# 2278657L.net
KiCad netlist of a schematic drawn in EAGLE
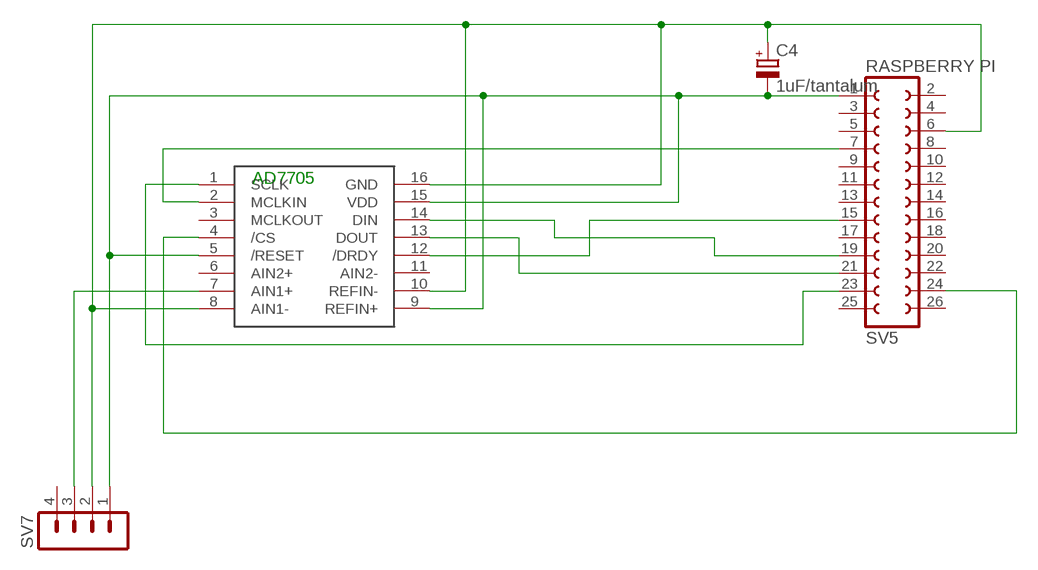
[diagram p0: schematic, sheet 1]

(export (version "E")
  (design (tool "Eeschema 10.0.6"))
  (components
    (comp (ref "C4")
      (value "1uF/tantalum")
      (footprint "eagle-import:TT2D7")
      (libsource (lib "eagle-import") (part "CPOL-EUTT2D7"))
    )
    (comp (ref "SV5")
      (value "RASPBERRY PI")
      (footprint "eagle-import:FE13-2")
      (libsource (lib "eagle-import") (part "FE13-2"))
    )
    (comp (ref "SV7")
      (value "MA04-1")
      (footprint "eagle-import:MA04-1")
      (libsource (lib "eagle-import") (part "MA04-1"))
    )
    (comp (ref "U$3")
      (value "AD7705")
      (footprint "eagle-import:DIP16")
      (libsource (lib "eagle-import") (part "AD7705"))
    )
  )
  (nets
    (net (code "1") (name "Net-(U$3-AIN1+)") (class "Default")
      (node (ref "SV7") (pin "3") (pinfunction "3_3") (pintype "passive"))
      (node (ref "U$3") (pin "7") (pinfunction "AIN1+_7") (pintype "bidirectional"))
    )
    (net (code "2") (name "Net-(U$3-AIN1-)") (class "Default")
      (node (ref "C4") (pin "+") (pinfunction "+_+") (pintype "passive"))
      (node (ref "SV5") (pin "6") (pinfunction "6_6") (pintype "passive"))
      (node (ref "SV7") (pin "2") (pinfunction "2_2") (pintype "passive"))
      (node (ref "U$3") (pin "10") (pinfunction "REFIN-_10") (pintype "bidirectional"))
      (node (ref "U$3") (pin "16") (pinfunction "GND_16") (pintype "power_in"))
      (node (ref "U$3") (pin "8") (pinfunction "AIN1-_8") (pintype "bidirectional"))
    )
    (net (code "3") (name "Net-(U$3-DIN)") (class "Default")
      (node (ref "SV5") (pin "19") (pinfunction "19_19") (pintype "passive"))
      (node (ref "U$3") (pin "14") (pinfunction "DIN_14") (pintype "bidirectional"))
    )
    (net (code "4") (name "Net-(U$3-DOUT)") (class "Default")
      (node (ref "SV5") (pin "21") (pinfunction "21_21") (pintype "passive"))
      (node (ref "U$3") (pin "13") (pinfunction "DOUT_13") (pintype "bidirectional"))
    )
    (net (code "5") (name "Net-(U$3-MCLKIN)") (class "Default")
      (node (ref "SV5") (pin "7") (pinfunction "7_7") (pintype "passive"))
      (node (ref "U$3") (pin "2") (pinfunction "MCLKIN_2") (pintype "bidirectional"))
    )
    (net (code "6") (name "Net-(U$3-REFIN+)") (class "Default")
      (node (ref "C4") (pin "-") (pinfunction "-_-") (pintype "passive"))
      (node (ref "SV5") (pin "1") (pinfunction "1_1") (pintype "passive"))
      (node (ref "SV7") (pin "1") (pinfunction "1_1") (pintype "passive"))
      (node (ref "U$3") (pin "15") (pinfunction "VDD_15") (pintype "power_in"))
      (node (ref "U$3") (pin "5") (pinfunction "/RESET_5") (pintype "bidirectional"))
      (node (ref "U$3") (pin "9") (pinfunction "REFIN+_9") (pintype "bidirectional"))
    )
    (net (code "7") (name "Net-(U$3-SCLK)") (class "Default")
      (node (ref "SV5") (pin "23") (pinfunction "23_23") (pintype "passive"))
      (node (ref "U$3") (pin "1") (pinfunction "SCLK_1") (pintype "bidirectional"))
    )
    (net (code "8") (name "Net-(U$3-{slash}CS)") (class "Default")
      (node (ref "SV5") (pin "24") (pinfunction "24_24") (pintype "passive"))
      (node (ref "U$3") (pin "4") (pinfunction "/CS_4") (pintype "bidirectional"))
    )
    (net (code "9") (name "Net-(U$3-{slash}DRDY)") (class "Default")
      (node (ref "SV5") (pin "15") (pinfunction "15_15") (pintype "passive"))
      (node (ref "U$3") (pin "12") (pinfunction "/DRDY_12") (pintype "bidirectional"))
    )
    (net (code "10") (name "unconnected-(SV5-Pad2)") (class "Default")
      (node (ref "SV5") (pin "2") (pinfunction "2_2") (pintype "passive"))
    )
    (net (code "11") (name "unconnected-(SV5-Pad3)") (class "Default")
      (node (ref "SV5") (pin "3") (pinfunction "3_3") (pintype "passive"))
    )
    (net (code "12") (name "unconnected-(SV5-Pad4)") (class "Default")
      (node (ref "SV5") (pin "4") (pinfunction "4_4") (pintype "passive"))
    )
    (net (code "13") (name "unconnected-(SV5-Pad5)") (class "Default")
      (node (ref "SV5") (pin "5") (pinfunction "5_5") (pintype "passive"))
    )
    (net (code "14") (name "unconnected-(SV5-Pad8)") (class "Default")
      (node (ref "SV5") (pin "8") (pinfunction "8_8") (pintype "passive"))
    )
    (net (code "15") (name "unconnected-(SV5-Pad9)") (class "Default")
      (node (ref "SV5") (pin "9") (pinfunction "9_9") (pintype "passive"))
    )
    (net (code "16") (name "unconnected-(SV5-Pad10)") (class "Default")
      (node (ref "SV5") (pin "10") (pinfunction "10_10") (pintype "passive"))
    )
    (net (code "17") (name "unconnected-(SV5-Pad11)") (class "Default")
      (node (ref "SV5") (pin "11") (pinfunction "11_11") (pintype "passive"))
    )
    (net (code "18") (name "unconnected-(SV5-Pad12)") (class "Default")
      (node (ref "SV5") (pin "12") (pinfunction "12_12") (pintype "passive"))
    )
    (net (code "19") (name "unconnected-(SV5-Pad13)") (class "Default")
      (node (ref "SV5") (pin "13") (pinfunction "13_13") (pintype "passive"))
    )
    (net (code "20") (name "unconnected-(SV5-Pad14)") (class "Default")
      (node (ref "SV5") (pin "14") (pinfunction "14_14") (pintype "passive"))
    )
    (net (code "21") (name "unconnected-(SV5-Pad16)") (class "Default")
      (node (ref "SV5") (pin "16") (pinfunction "16_16") (pintype "passive"))
    )
    (net (code "22") (name "unconnected-(SV5-Pad17)") (class "Default")
      (node (ref "SV5") (pin "17") (pinfunction "17_17") (pintype "passive"))
    )
    (net (code "23") (name "unconnected-(SV5-Pad18)") (class "Default")
      (node (ref "SV5") (pin "18") (pinfunction "18_18") (pintype "passive"))
    )
    (net (code "24") (name "unconnected-(SV5-Pad20)") (class "Default")
      (node (ref "SV5") (pin "20") (pinfunction "20_20") (pintype "passive"))
    )
    (net (code "25") (name "unconnected-(SV5-Pad22)") (class "Default")
      (node (ref "SV5") (pin "22") (pinfunction "22_22") (pintype "passive"))
    )
    (net (code "26") (name "unconnected-(SV5-Pad25)") (class "Default")
      (node (ref "SV5") (pin "25") (pinfunction "25_25") (pintype "passive"))
    )
    (net (code "27") (name "unconnected-(SV5-Pad26)") (class "Default")
      (node (ref "SV5") (pin "26") (pinfunction "26_26") (pintype "passive"))
    )
    (net (code "28") (name "unconnected-(SV7-Pad4)") (class "Default")
      (node (ref "SV7") (pin "4") (pinfunction "4_4") (pintype "passive"))
    )
    (net (code "29") (name "unconnected-(U$3-AIN2+-Pad6)") (class "Default")
      (node (ref "U$3") (pin "6") (pinfunction "AIN2+_6") (pintype "bidirectional"))
    )
    (net (code "30") (name "unconnected-(U$3-AIN2--Pad11)") (class "Default")
      (node (ref "U$3") (pin "11") (pinfunction "AIN2-_11") (pintype "bidirectional"))
    )
    (net (code "31") (name "unconnected-(U$3-MCLKOUT-Pad3)") (class "Default")
      (node (ref "U$3") (pin "3") (pinfunction "MCLKOUT_3") (pintype "bidirectional"))
    )
  )
)
